# Encoder_NPN.net
KiCad netlist of a schematic drawn in Altium Designer
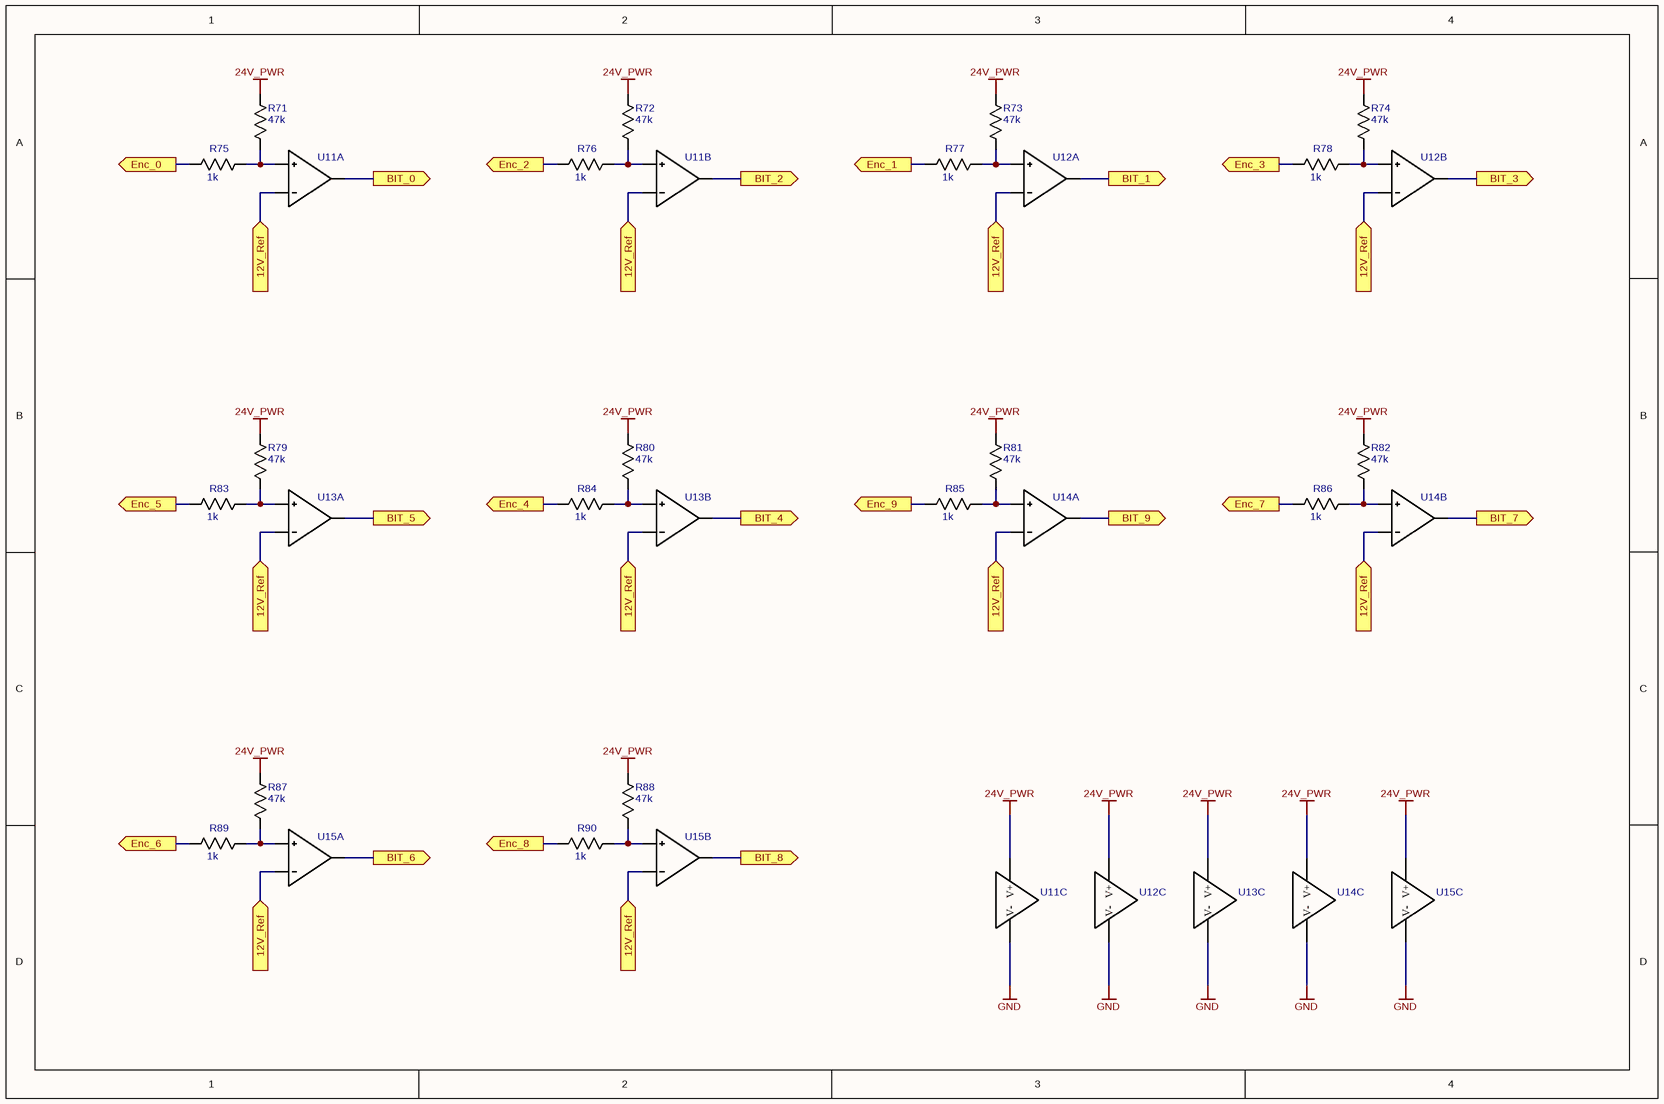
[diagram p0: Encoder NPN.SchDoc]

(export (version "E")
  (design (tool "Eeschema 10.0.6"))
  (components
    (comp (ref "R71")
      (value "47k")
      (footprint "RES 0603")
      (description "RC0603FR-0747KL")
      (libsource (lib "levin") (part "Resistor"))
    )
    (comp (ref "R72")
      (value "47k")
      (footprint "RES 0603")
      (description "RC0603FR-0747KL")
      (libsource (lib "levin") (part "Resistor"))
    )
    (comp (ref "R73")
      (value "47k")
      (footprint "RES 0603")
      (description "RC0603FR-0747KL")
      (libsource (lib "levin") (part "Resistor"))
    )
    (comp (ref "R74")
      (value "47k")
      (footprint "RES 0603")
      (description "RC0603FR-0747KL")
      (libsource (lib "levin") (part "Resistor"))
    )
    (comp (ref "R75")
      (value "1k")
      (footprint "RES 0603")
      (description "RC0603FR-071KL")
      (libsource (lib "levin") (part "Resistor"))
    )
    (comp (ref "R76")
      (value "1k")
      (footprint "RES 0603")
      (description "RC0603FR-071KL")
      (libsource (lib "levin") (part "Resistor"))
    )
    (comp (ref "R77")
      (value "1k")
      (footprint "RES 0603")
      (description "RC0603FR-071KL")
      (libsource (lib "levin") (part "Resistor"))
    )
    (comp (ref "R78")
      (value "1k")
      (footprint "RES 0603")
      (description "RC0603FR-071KL")
      (libsource (lib "levin") (part "Resistor"))
    )
    (comp (ref "R79")
      (value "47k")
      (footprint "RES 0603")
      (description "RC0603FR-0747KL")
      (libsource (lib "levin") (part "Resistor"))
    )
    (comp (ref "R80")
      (value "47k")
      (footprint "RES 0603")
      (description "RC0603FR-0747KL")
      (libsource (lib "levin") (part "Resistor"))
    )
    (comp (ref "R81")
      (value "47k")
      (footprint "RES 0603")
      (description "RC0603FR-0747KL")
      (libsource (lib "levin") (part "Resistor"))
    )
    (comp (ref "R82")
      (value "47k")
      (footprint "RES 0603")
      (description "RC0603FR-0747KL")
      (libsource (lib "levin") (part "Resistor"))
    )
    (comp (ref "R83")
      (value "1k")
      (footprint "RES 0603")
      (description "RC0603FR-071KL")
      (libsource (lib "levin") (part "Resistor"))
    )
    (comp (ref "R84")
      (value "1k")
      (footprint "RES 0603")
      (description "RC0603FR-071KL")
      (libsource (lib "levin") (part "Resistor"))
    )
    (comp (ref "R85")
      (value "1k")
      (footprint "RES 0603")
      (description "RC0603FR-071KL")
      (libsource (lib "levin") (part "Resistor"))
    )
    (comp (ref "R86")
      (value "1k")
      (footprint "RES 0603")
      (description "RC0603FR-071KL")
      (libsource (lib "levin") (part "Resistor"))
    )
    (comp (ref "R87")
      (value "47k")
      (footprint "RES 0603")
      (description "RC0603FR-0747KL")
      (libsource (lib "levin") (part "Resistor"))
    )
    (comp (ref "R88")
      (value "47k")
      (footprint "RES 0603")
      (description "RC0603FR-0747KL")
      (libsource (lib "levin") (part "Resistor"))
    )
    (comp (ref "R89")
      (value "1k")
      (footprint "RES 0603")
      (description "RC0603FR-071KL")
      (libsource (lib "levin") (part "Resistor"))
    )
    (comp (ref "R90")
      (value "1k")
      (footprint "RES 0603")
      (description "RC0603FR-071KL")
      (libsource (lib "levin") (part "Resistor"))
    )
    (comp (ref "U11")
      (value "Comparator x2 Small")
      (footprint "SOIC-8")
      (description "LM2903")
      (libsource (lib "levin") (part "Comparator x2 Small"))
    )
    (comp (ref "U12")
      (value "Comparator x2 Small")
      (footprint "SOIC-8")
      (description "LM2903")
      (libsource (lib "levin") (part "Comparator x2 Small"))
    )
    (comp (ref "U13")
      (value "Comparator x2 Small")
      (footprint "SOIC-8")
      (description "LM2903")
      (libsource (lib "levin") (part "Comparator x2 Small"))
    )
    (comp (ref "U14")
      (value "Comparator x2 Small")
      (footprint "SOIC-8")
      (description "LM2903")
      (libsource (lib "levin") (part "Comparator x2 Small"))
    )
    (comp (ref "U15")
      (value "Comparator x2 Small")
      (footprint "SOIC-8")
      (description "LM2903")
      (libsource (lib "levin") (part "Comparator x2 Small"))
    )
  )
  (nets
    (net (code "1") (name "/12V_Ref") (class "Default")
      (node (ref "U11") (pin "2") (pinfunction "-IN_2") (pintype "passive"))
      (node (ref "U11") (pin "5") (pinfunction "-IN_5") (pintype "passive"))
      (node (ref "U12") (pin "2") (pinfunction "-IN_2") (pintype "passive"))
      (node (ref "U12") (pin "5") (pinfunction "-IN_5") (pintype "passive"))
      (node (ref "U13") (pin "2") (pinfunction "-IN_2") (pintype "passive"))
      (node (ref "U13") (pin "5") (pinfunction "-IN_5") (pintype "passive"))
      (node (ref "U14") (pin "2") (pinfunction "-IN_2") (pintype "passive"))
      (node (ref "U14") (pin "5") (pinfunction "-IN_5") (pintype "passive"))
      (node (ref "U15") (pin "2") (pinfunction "-IN_2") (pintype "passive"))
      (node (ref "U15") (pin "5") (pinfunction "-IN_5") (pintype "passive"))
    )
    (net (code "2") (name "/BIT_0") (class "Default")
      (node (ref "U11") (pin "3") (pinfunction "OUT_3") (pintype "passive"))
    )
    (net (code "3") (name "/BIT_1") (class "Default")
      (node (ref "U12") (pin "3") (pinfunction "OUT_3") (pintype "passive"))
    )
    (net (code "4") (name "/BIT_2") (class "Default")
      (node (ref "U11") (pin "6") (pinfunction "OUT_6") (pintype "passive"))
    )
    (net (code "5") (name "/BIT_3") (class "Default")
      (node (ref "U12") (pin "6") (pinfunction "OUT_6") (pintype "passive"))
    )
    (net (code "6") (name "/BIT_4") (class "Default")
      (node (ref "U13") (pin "6") (pinfunction "OUT_6") (pintype "passive"))
    )
    (net (code "7") (name "/BIT_5") (class "Default")
      (node (ref "U13") (pin "3") (pinfunction "OUT_3") (pintype "passive"))
    )
    (net (code "8") (name "/BIT_6") (class "Default")
      (node (ref "U15") (pin "3") (pinfunction "OUT_3") (pintype "passive"))
    )
    (net (code "9") (name "/BIT_7") (class "Default")
      (node (ref "U14") (pin "6") (pinfunction "OUT_6") (pintype "passive"))
    )
    (net (code "10") (name "/BIT_8") (class "Default")
      (node (ref "U15") (pin "6") (pinfunction "OUT_6") (pintype "passive"))
    )
    (net (code "11") (name "/BIT_9") (class "Default")
      (node (ref "U14") (pin "3") (pinfunction "OUT_3") (pintype "passive"))
    )
    (net (code "12") (name "/Enc_0") (class "Default")
      (node (ref "R75") (pin "2") (pinfunction "2_2") (pintype "passive"))
    )
    (net (code "13") (name "/Enc_1") (class "Default")
      (node (ref "R77") (pin "2") (pinfunction "2_2") (pintype "passive"))
    )
    (net (code "14") (name "/Enc_2") (class "Default")
      (node (ref "R76") (pin "2") (pinfunction "2_2") (pintype "passive"))
    )
    (net (code "15") (name "/Enc_3") (class "Default")
      (node (ref "R78") (pin "2") (pinfunction "2_2") (pintype "passive"))
    )
    (net (code "16") (name "/Enc_4") (class "Default")
      (node (ref "R84") (pin "2") (pinfunction "2_2") (pintype "passive"))
    )
    (net (code "17") (name "/Enc_5") (class "Default")
      (node (ref "R83") (pin "2") (pinfunction "2_2") (pintype "passive"))
    )
    (net (code "18") (name "/Enc_6") (class "Default")
      (node (ref "R89") (pin "2") (pinfunction "2_2") (pintype "passive"))
    )
    (net (code "19") (name "/Enc_7") (class "Default")
      (node (ref "R86") (pin "2") (pinfunction "2_2") (pintype "passive"))
    )
    (net (code "20") (name "/Enc_8") (class "Default")
      (node (ref "R90") (pin "2") (pinfunction "2_2") (pintype "passive"))
    )
    (net (code "21") (name "/Enc_9") (class "Default")
      (node (ref "R85") (pin "2") (pinfunction "2_2") (pintype "passive"))
    )
    (net (code "22") (name "24V_PWR") (class "Default")
      (node (ref "R71") (pin "2") (pinfunction "2_2") (pintype "passive"))
      (node (ref "R72") (pin "2") (pinfunction "2_2") (pintype "passive"))
      (node (ref "R73") (pin "2") (pinfunction "2_2") (pintype "passive"))
      (node (ref "R74") (pin "2") (pinfunction "2_2") (pintype "passive"))
      (node (ref "R79") (pin "2") (pinfunction "2_2") (pintype "passive"))
      (node (ref "R80") (pin "2") (pinfunction "2_2") (pintype "passive"))
      (node (ref "R81") (pin "2") (pinfunction "2_2") (pintype "passive"))
      (node (ref "R82") (pin "2") (pinfunction "2_2") (pintype "passive"))
      (node (ref "R87") (pin "2") (pinfunction "2_2") (pintype "passive"))
      (node (ref "R88") (pin "2") (pinfunction "2_2") (pintype "passive"))
      (node (ref "U11") (pin "7") (pinfunction "V+_7") (pintype "passive"))
      (node (ref "U12") (pin "7") (pinfunction "V+_7") (pintype "passive"))
      (node (ref "U13") (pin "7") (pinfunction "V+_7") (pintype "passive"))
      (node (ref "U14") (pin "7") (pinfunction "V+_7") (pintype "passive"))
      (node (ref "U15") (pin "7") (pinfunction "V+_7") (pintype "passive"))
    )
    (net (code "23") (name "GND") (class "Default")
      (node (ref "U11") (pin "8") (pinfunction "V-_8") (pintype "passive"))
      (node (ref "U12") (pin "8") (pinfunction "V-_8") (pintype "passive"))
      (node (ref "U13") (pin "8") (pinfunction "V-_8") (pintype "passive"))
      (node (ref "U14") (pin "8") (pinfunction "V-_8") (pintype "passive"))
      (node (ref "U15") (pin "8") (pinfunction "V-_8") (pintype "passive"))
    )
    (net (code "24") (name "Net-(U11A-+IN)") (class "Default")
      (node (ref "R71") (pin "1") (pinfunction "1_1") (pintype "passive"))
      (node (ref "R75") (pin "1") (pinfunction "1_1") (pintype "passive"))
      (node (ref "U11") (pin "1") (pinfunction "+IN_1") (pintype "passive"))
    )
    (net (code "25") (name "Net-(U11B-+IN)") (class "Default")
      (node (ref "R72") (pin "1") (pinfunction "1_1") (pintype "passive"))
      (node (ref "R76") (pin "1") (pinfunction "1_1") (pintype "passive"))
      (node (ref "U11") (pin "4") (pinfunction "+IN_4") (pintype "passive"))
    )
    (net (code "26") (name "Net-(U12A-+IN)") (class "Default")
      (node (ref "R73") (pin "1") (pinfunction "1_1") (pintype "passive"))
      (node (ref "R77") (pin "1") (pinfunction "1_1") (pintype "passive"))
      (node (ref "U12") (pin "1") (pinfunction "+IN_1") (pintype "passive"))
    )
    (net (code "27") (name "Net-(U12B-+IN)") (class "Default")
      (node (ref "R74") (pin "1") (pinfunction "1_1") (pintype "passive"))
      (node (ref "R78") (pin "1") (pinfunction "1_1") (pintype "passive"))
      (node (ref "U12") (pin "4") (pinfunction "+IN_4") (pintype "passive"))
    )
    (net (code "28") (name "Net-(U13A-+IN)") (class "Default")
      (node (ref "R79") (pin "1") (pinfunction "1_1") (pintype "passive"))
      (node (ref "R83") (pin "1") (pinfunction "1_1") (pintype "passive"))
      (node (ref "U13") (pin "1") (pinfunction "+IN_1") (pintype "passive"))
    )
    (net (code "29") (name "Net-(U13B-+IN)") (class "Default")
      (node (ref "R80") (pin "1") (pinfunction "1_1") (pintype "passive"))
      (node (ref "R84") (pin "1") (pinfunction "1_1") (pintype "passive"))
      (node (ref "U13") (pin "4") (pinfunction "+IN_4") (pintype "passive"))
    )
    (net (code "30") (name "Net-(U14A-+IN)") (class "Default")
      (node (ref "R81") (pin "1") (pinfunction "1_1") (pintype "passive"))
      (node (ref "R85") (pin "1") (pinfunction "1_1") (pintype "passive"))
      (node (ref "U14") (pin "1") (pinfunction "+IN_1") (pintype "passive"))
    )
    (net (code "31") (name "Net-(U14B-+IN)") (class "Default")
      (node (ref "R82") (pin "1") (pinfunction "1_1") (pintype "passive"))
      (node (ref "R86") (pin "1") (pinfunction "1_1") (pintype "passive"))
      (node (ref "U14") (pin "4") (pinfunction "+IN_4") (pintype "passive"))
    )
    (net (code "32") (name "Net-(U15A-+IN)") (class "Default")
      (node (ref "R87") (pin "1") (pinfunction "1_1") (pintype "passive"))
      (node (ref "R89") (pin "1") (pinfunction "1_1") (pintype "passive"))
      (node (ref "U15") (pin "1") (pinfunction "+IN_1") (pintype "passive"))
    )
    (net (code "33") (name "Net-(U15B-+IN)") (class "Default")
      (node (ref "R88") (pin "1") (pinfunction "1_1") (pintype "passive"))
      (node (ref "R90") (pin "1") (pinfunction "1_1") (pintype "passive"))
      (node (ref "U15") (pin "4") (pinfunction "+IN_4") (pintype "passive"))
    )
  )
)
